# HalfA.net
KiCad netlist of a schematic drawn in EAGLE
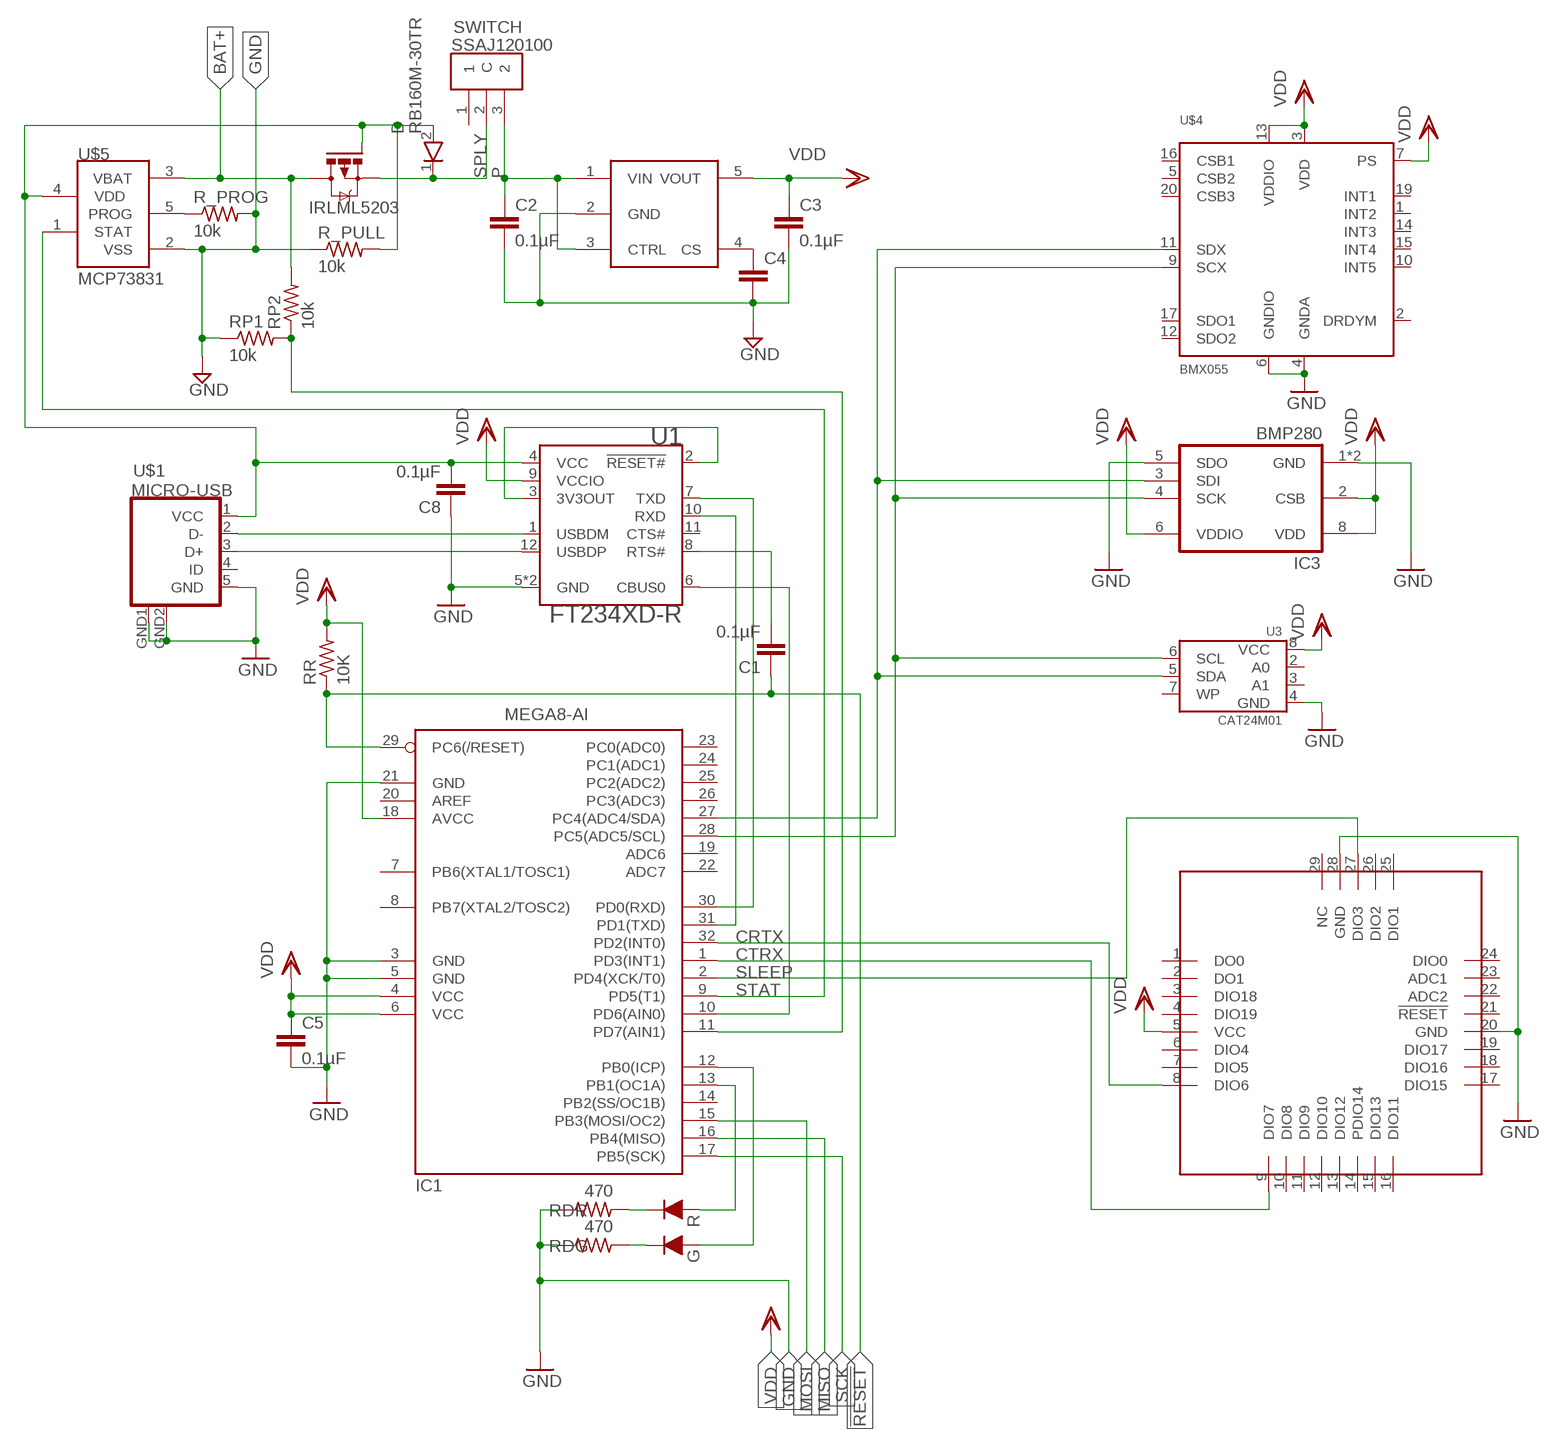
[diagram p0: schematic, sheet 1]

(export (version "E")
  (design (tool "Eeschema 10.0.6"))
  (components
    (comp (ref "C1")
      (value "0.1µF")
      (footprint "eagle-import:C0402K")
      (libsource (lib "eagle-import") (part "C-EUC0402K"))
    )
    (comp (ref "C2")
      (value "0.1µF")
      (footprint "eagle-import:C0402K")
      (libsource (lib "eagle-import") (part "C-EUC0402K"))
    )
    (comp (ref "C3")
      (value "0.1µF")
      (footprint "eagle-import:C0402K")
      (libsource (lib "eagle-import") (part "C-EUC0402K"))
    )
    (comp (ref "C4")
      (value "C-EUC0402K")
      (footprint "eagle-import:C0402K")
      (libsource (lib "eagle-import") (part "C-EUC0402K"))
    )
    (comp (ref "C5")
      (value "0.1µF")
      (footprint "eagle-import:C0402K")
      (libsource (lib "eagle-import") (part "C-EUC0402K"))
    )
    (comp (ref "C8")
      (value "0.1µF")
      (footprint "eagle-import:C0402K")
      (libsource (lib "eagle-import") (part "C-EUC0402K"))
    )
    (comp (ref "D")
      (value "RB160M-30TR")
      (footprint "eagle-import:SODFL3516X90N")
      (fields (field (name "MOUSER_PART_NUMBER") "755-RB160M-30TR") (field (name "RS_PART_NUMBER") "7526079"))
      (libsource (lib "eagle-import") (part "RB160M-30TR"))
    )
    (comp (ref "IC1")
      (value "MEGA8-AI")
      (footprint "eagle-import:TQFP32-08")
      (fields (field (name "MPN") "ATMEGA8-16AU"))
      (libsource (lib "eagle-import") (part "MEGA8-AI"))
    )
    (comp (ref "IC3")
      (value "BMP280")
      (footprint "eagle-import:BMP280")
      (libsource (lib "eagle-import") (part "BMP280"))
    )
    (comp (ref "Q1")
      (value "IRLML5203")
      (footprint "eagle-import:MICRO3")
      (libsource (lib "eagle-import") (part "IRLML5203"))
    )
    (comp (ref "RDG")
      (value "470")
      (footprint "eagle-import:R0402")
      (libsource (lib "eagle-import") (part "R-US_R0402"))
    )
    (comp (ref "RDR")
      (value "470")
      (footprint "eagle-import:R0402")
      (libsource (lib "eagle-import") (part "R-US_R0402"))
    )
    (comp (ref "RP1")
      (value "10k")
      (footprint "eagle-import:R0402")
      (libsource (lib "eagle-import") (part "R-US_R0402"))
    )
    (comp (ref "RP2")
      (value "10k")
      (footprint "eagle-import:R0402")
      (libsource (lib "eagle-import") (part "R-US_R0402"))
    )
    (comp (ref "RR")
      (value "10K")
      (footprint "eagle-import:R0402")
      (libsource (lib "eagle-import") (part "R-US_R0402"))
    )
    (comp (ref "R_PROG")
      (value "10k")
      (footprint "eagle-import:R0402")
      (libsource (lib "eagle-import") (part "R-US_R0402"))
    )
    (comp (ref "R_PULL")
      (value "10k")
      (footprint "eagle-import:R0402")
      (libsource (lib "eagle-import") (part "R-US_R0402"))
    )
    (comp (ref "SWITCH")
      (value "SSAJ120100")
      (footprint "eagle-import:SSAJ120100")
      (fields (field (name "MOUSER_PART_NUMBER") "688-SSAJ120100") (field (name "RS_PART_NUMBER") "1238892"))
      (libsource (lib "eagle-import") (part "SSAJ120100"))
    )
    (comp (ref "U$1")
      (value "MICRO-USB")
      (footprint "eagle-import:MICRO-USB")
      (libsource (lib "eagle-import") (part "MICRO-USB"))
    )
    (comp (ref "U$2")
      (value "NJM12888F")
      (footprint "eagle-import:NJM12888F")
      (libsource (lib "eagle-import") (part "NJM12888F"))
    )
    (comp (ref "U$3")
      (value "LITE")
      (footprint "eagle-import:LITE")
      (libsource (lib "eagle-import") (part "LITE"))
    )
    (comp (ref "U$4")
      (value "BMX055")
      (footprint "eagle-import:BMX055")
      (fields (field (name "DIGI-KEY_PART_NUMBER") "828-1060-1-ND") (field (name "MF") "Bosch Sensortec"))
      (libsource (lib "eagle-import") (part "BMX055"))
    )
    (comp (ref "U$5")
      (value "MCP73831")
      (footprint "eagle-import:SOT23-5L")
      (libsource (lib "eagle-import") (part "MCP73831"))
    )
    (comp (ref "U$6")
      (value "SML-P24MUW")
      (footprint "eagle-import:SML-P24MUW")
      (libsource (lib "eagle-import") (part "SML-P24MUW"))
    )
    (comp (ref "U1")
      (value "FT234XD-R")
      (footprint "eagle-import:SON45P300X300X80-13N")
      (fields (field (name "DIGI-KEY_PART_NUMBER") "768-1178-1-ND") (field (name "MF") "FTDI,"))
      (libsource (lib "eagle-import") (part "FT234XD-R"))
    )
    (comp (ref "U3")
      (value "CAT24M01")
      (footprint "eagle-import:SO-8")
      (fields (field (name "MF") "ON Semiconductor"))
      (libsource (lib "eagle-import") (part "CAT24M01"))
    )
  )
  (nets
    (net (code "1") (name "/CRTX") (class "Default")
      (node (ref "IC1") (pin "32") (pinfunction "PD2(INT0)_32") (pintype "bidirectional"))
      (node (ref "U$3") (pin "8") (pinfunction "DIO6_8") (pintype "bidirectional"))
    )
    (net (code "2") (name "/CTRX") (class "Default")
      (node (ref "IC1") (pin "1") (pinfunction "PD3(INT1)_1") (pintype "bidirectional"))
      (node (ref "U$3") (pin "9") (pinfunction "DIO7_9") (pintype "bidirectional"))
    )
    (net (code "3") (name "/P") (class "Default")
      (node (ref "C2") (pin "1") (pinfunction "1_1") (pintype "passive"))
      (node (ref "SWITCH") (pin "3") (pinfunction "2_3") (pintype "bidirectional"))
      (node (ref "U$2") (pin "1") (pinfunction "VIN_1") (pintype "power_in"))
      (node (ref "U$2") (pin "3") (pinfunction "CTRL_3") (pintype "input"))
    )
    (net (code "4") (name "/SLEEP") (class "Default")
      (node (ref "IC1") (pin "2") (pinfunction "PD4(XCK/T0)_2") (pintype "bidirectional"))
      (node (ref "U$3") (pin "27") (pinfunction "DIO3_27") (pintype "bidirectional"))
    )
    (net (code "5") (name "/SPLY") (class "Default")
      (node (ref "D") (pin "1") (pinfunction "K_1") (pintype "bidirectional"))
      (node (ref "Q1") (pin "2") (pinfunction "S_2") (pintype "passive"))
      (node (ref "SWITCH") (pin "2") (pinfunction "C_2") (pintype "bidirectional"))
    )
    (net (code "6") (name "/STAT") (class "Default")
      (node (ref "IC1") (pin "9") (pinfunction "PD5(T1)_9") (pintype "bidirectional"))
      (node (ref "U$5") (pin "1") (pinfunction "STAT_1") (pintype "bidirectional"))
    )
    (net (code "7") (name "/~{RESET}") (class "Default")
      (node (ref "C1") (pin "1") (pinfunction "1_1") (pintype "passive"))
      (node (ref "IC1") (pin "29") (pinfunction "PC6(/RESET)_29") (pintype "bidirectional"))
      (node (ref "RR") (pin "1") (pinfunction "1_1") (pintype "passive"))
    )
    (net (code "8") (name "BAT+") (class "Default")
      (node (ref "Q1") (pin "3") (pinfunction "D_3") (pintype "passive"))
      (node (ref "RP2") (pin "2") (pinfunction "2_2") (pintype "passive"))
      (node (ref "U$5") (pin "3") (pinfunction "VBAT_3") (pintype "bidirectional"))
    )
    (net (code "9") (name "GND") (class "Default")
      (node (ref "C2") (pin "2") (pinfunction "2_2") (pintype "passive"))
      (node (ref "C3") (pin "2") (pinfunction "2_2") (pintype "passive"))
      (node (ref "C4") (pin "2") (pinfunction "2_2") (pintype "passive"))
      (node (ref "C5") (pin "2") (pinfunction "2_2") (pintype "passive"))
      (node (ref "C8") (pin "1") (pinfunction "1_1") (pintype "passive"))
      (node (ref "IC1") (pin "21") (pinfunction "GND_21") (pintype "power_in"))
      (node (ref "IC1") (pin "3") (pinfunction "GND_3") (pintype "power_in"))
      (node (ref "IC1") (pin "5") (pinfunction "GND_5") (pintype "power_in"))
      (node (ref "IC3") (pin "1") (pinfunction "GND_1") (pintype "power_in"))
      (node (ref "IC3") (pin "5") (pinfunction "SDO_5") (pintype "input"))
      (node (ref "IC3") (pin "7") (pinfunction "GND_7") (pintype "power_in"))
      (node (ref "RDG") (pin "1") (pinfunction "1_1") (pintype "passive"))
      (node (ref "RDR") (pin "1") (pinfunction "1_1") (pintype "passive"))
      (node (ref "RP1") (pin "1") (pinfunction "1_1") (pintype "passive"))
      (node (ref "R_PROG") (pin "2") (pinfunction "2_2") (pintype "passive"))
      (node (ref "R_PULL") (pin "1") (pinfunction "1_1") (pintype "passive"))
      (node (ref "U$1") (pin "5") (pinfunction "GND_5") (pintype "power_in"))
      (node (ref "U$1") (pin "GND1") (pinfunction "GND_GND1") (pintype "power_in"))
      (node (ref "U$1") (pin "GND2") (pinfunction "GND_GND2") (pintype "power_in"))
      (node (ref "U$2") (pin "2") (pinfunction "GND_2") (pintype "power_in"))
      (node (ref "U$3") (pin "20") (pinfunction "GND_20") (pintype "power_in"))
      (node (ref "U$3") (pin "28") (pinfunction "GND_28") (pintype "power_in"))
      (node (ref "U$4") (pin "4") (pinfunction "GNDA_4") (pintype "bidirectional"))
      (node (ref "U$4") (pin "6") (pinfunction "GNDIO_6") (pintype "bidirectional"))
      (node (ref "U$5") (pin "2") (pinfunction "VSS_2") (pintype "bidirectional"))
      (node (ref "U1") (pin "13") (pinfunction "GND_13") (pintype "power_in"))
      (node (ref "U1") (pin "5") (pinfunction "GND_5") (pintype "power_in"))
      (node (ref "U3") (pin "4") (pinfunction "GND_4") (pintype "bidirectional"))
    )
    (net (code "10") (name "MISO") (class "Default")
      (node (ref "IC1") (pin "16") (pinfunction "PB4(MISO)_16") (pintype "bidirectional"))
    )
    (net (code "11") (name "MOSI") (class "Default")
      (node (ref "IC1") (pin "15") (pinfunction "PB3(MOSI/OC2)_15") (pintype "bidirectional"))
    )
    (net (code "12") (name "Net-(D-A)") (class "Default")
      (node (ref "C8") (pin "2") (pinfunction "2_2") (pintype "passive"))
      (node (ref "D") (pin "2") (pinfunction "A_2") (pintype "bidirectional"))
      (node (ref "Q1") (pin "1") (pinfunction "G_1") (pintype "passive"))
      (node (ref "R_PULL") (pin "2") (pinfunction "2_2") (pintype "passive"))
      (node (ref "U$1") (pin "1") (pinfunction "VCC_1") (pintype "power_in"))
      (node (ref "U$5") (pin "4") (pinfunction "VDD_4") (pintype "bidirectional"))
      (node (ref "U1") (pin "4") (pinfunction "VCC_4") (pintype "power_in"))
    )
    (net (code "13") (name "Net-(IC1-PB0(ICP))") (class "Default")
      (node (ref "IC1") (pin "12") (pinfunction "PB0(ICP)_12") (pintype "bidirectional"))
      (node (ref "U$6") (pin "1") (pinfunction "GA_1") (pintype "power_in"))
    )
    (net (code "14") (name "Net-(IC1-PB1(OC1A))") (class "Default")
      (node (ref "IC1") (pin "13") (pinfunction "PB1(OC1A)_13") (pintype "bidirectional"))
      (node (ref "U$6") (pin "2") (pinfunction "RA_2") (pintype "power_in"))
    )
    (net (code "15") (name "Net-(IC1-PC4(ADC4{slash}SDA))") (class "Default")
      (node (ref "IC1") (pin "27") (pinfunction "PC4(ADC4/SDA)_27") (pintype "bidirectional"))
      (node (ref "IC3") (pin "3") (pinfunction "SDI_3") (pintype "bidirectional"))
      (node (ref "U$4") (pin "11") (pinfunction "SDX_11") (pintype "bidirectional"))
      (node (ref "U3") (pin "5") (pinfunction "SDA_5") (pintype "bidirectional"))
    )
    (net (code "16") (name "Net-(IC1-PC5(ADC5{slash}SCL))") (class "Default")
      (node (ref "IC1") (pin "28") (pinfunction "PC5(ADC5/SCL)_28") (pintype "bidirectional"))
      (node (ref "IC3") (pin "4") (pinfunction "SCK_4") (pintype "bidirectional"))
      (node (ref "U$4") (pin "9") (pinfunction "SCX_9") (pintype "bidirectional"))
      (node (ref "U3") (pin "6") (pinfunction "SCL_6") (pintype "bidirectional"))
    )
    (net (code "17") (name "Net-(IC1-PD0(RXD))") (class "Default")
      (node (ref "IC1") (pin "30") (pinfunction "PD0(RXD)_30") (pintype "bidirectional"))
      (node (ref "U1") (pin "7") (pinfunction "TXD_7") (pintype "output"))
    )
    (net (code "18") (name "Net-(IC1-PD1(TXD))") (class "Default")
      (node (ref "IC1") (pin "31") (pinfunction "PD1(TXD)_31") (pintype "bidirectional"))
      (node (ref "U1") (pin "10") (pinfunction "RXD_10") (pintype "input"))
    )
    (net (code "19") (name "Net-(IC1-PD6(AIN0))") (class "Default")
      (node (ref "IC1") (pin "10") (pinfunction "PD6(AIN0)_10") (pintype "bidirectional"))
      (node (ref "U1") (pin "6") (pinfunction "CBUS0_6") (pintype "bidirectional"))
    )
    (net (code "20") (name "Net-(IC1-PD7(AIN1))") (class "Default")
      (node (ref "IC1") (pin "11") (pinfunction "PD7(AIN1)_11") (pintype "bidirectional"))
      (node (ref "RP1") (pin "2") (pinfunction "2_2") (pintype "passive"))
      (node (ref "RP2") (pin "1") (pinfunction "1_1") (pintype "passive"))
    )
    (net (code "21") (name "Net-(U$1-D+)") (class "Default")
      (node (ref "U$1") (pin "3") (pinfunction "D+_3") (pintype "bidirectional"))
      (node (ref "U1") (pin "12") (pinfunction "USBDP_12") (pintype "bidirectional"))
    )
    (net (code "22") (name "Net-(U$1-D-)") (class "Default")
      (node (ref "U$1") (pin "2") (pinfunction "D-_2") (pintype "bidirectional"))
      (node (ref "U1") (pin "1") (pinfunction "USBDM_1") (pintype "bidirectional"))
    )
    (net (code "23") (name "Net-(U$2-CS)") (class "Default")
      (node (ref "C4") (pin "1") (pinfunction "1_1") (pintype "passive"))
      (node (ref "U$2") (pin "4") (pinfunction "CS_4") (pintype "input"))
    )
    (net (code "24") (name "Net-(U$5-PROG)") (class "Default")
      (node (ref "R_PROG") (pin "1") (pinfunction "1_1") (pintype "passive"))
      (node (ref "U$5") (pin "5") (pinfunction "PROG_5") (pintype "bidirectional"))
    )
    (net (code "25") (name "Net-(U$6-GC)") (class "Default")
      (node (ref "RDG") (pin "2") (pinfunction "2_2") (pintype "passive"))
      (node (ref "U$6") (pin "4") (pinfunction "GC_4") (pintype "power_in"))
    )
    (net (code "26") (name "Net-(U$6-RC)") (class "Default")
      (node (ref "RDR") (pin "2") (pinfunction "2_2") (pintype "passive"))
      (node (ref "U$6") (pin "3") (pinfunction "RC_3") (pintype "power_in"))
    )
    (net (code "27") (name "Net-(U1-3V3OUT)") (class "Default")
      (node (ref "U1") (pin "2") (pinfunction "~{RESET#}_2") (pintype "input"))
      (node (ref "U1") (pin "3") (pinfunction "3V3OUT_3") (pintype "power_in"))
    )
    (net (code "28") (name "Net-(U1-RTS#)") (class "Default")
      (node (ref "C1") (pin "2") (pinfunction "2_2") (pintype "passive"))
      (node (ref "U1") (pin "8") (pinfunction "RTS#_8") (pintype "output"))
    )
    (net (code "29") (name "SCK") (class "Default")
      (node (ref "IC1") (pin "17") (pinfunction "PB5(SCK)_17") (pintype "bidirectional"))
    )
    (net (code "30") (name "VDD") (class "Default")
      (node (ref "C3") (pin "1") (pinfunction "1_1") (pintype "passive"))
      (node (ref "C5") (pin "1") (pinfunction "1_1") (pintype "passive"))
      (node (ref "IC1") (pin "18") (pinfunction "AVCC_18") (pintype "power_in"))
      (node (ref "IC1") (pin "4") (pinfunction "VCC_4") (pintype "power_in"))
      (node (ref "IC1") (pin "6") (pinfunction "VCC_6") (pintype "power_in"))
      (node (ref "IC3") (pin "2") (pinfunction "CSB_2") (pintype "input"))
      (node (ref "IC3") (pin "6") (pinfunction "VDDIO_6") (pintype "power_in"))
      (node (ref "IC3") (pin "8") (pinfunction "VDD_8") (pintype "power_in"))
      (node (ref "RR") (pin "2") (pinfunction "2_2") (pintype "passive"))
      (node (ref "U$2") (pin "5") (pinfunction "VOUT_5") (pintype "power_in"))
      (node (ref "U$3") (pin "5") (pinfunction "VCC_5") (pintype "power_in"))
      (node (ref "U$4") (pin "13") (pinfunction "VDDIO_13") (pintype "bidirectional"))
      (node (ref "U$4") (pin "3") (pinfunction "VDD_3") (pintype "bidirectional"))
      (node (ref "U$4") (pin "7") (pinfunction "PS_7") (pintype "bidirectional"))
      (node (ref "U1") (pin "9") (pinfunction "VCCIO_9") (pintype "power_in"))
      (node (ref "U3") (pin "8") (pinfunction "VCC_8") (pintype "bidirectional"))
    )
    (net (code "31") (name "unconnected-(IC1-ADC6-Pad19)") (class "Default")
      (node (ref "IC1") (pin "19") (pinfunction "ADC6_19") (pintype "bidirectional"))
    )
    (net (code "32") (name "unconnected-(IC1-ADC7-Pad22)") (class "Default")
      (node (ref "IC1") (pin "22") (pinfunction "ADC7_22") (pintype "bidirectional"))
    )
    (net (code "33") (name "unconnected-(IC1-AREF-Pad20)") (class "Default")
      (node (ref "IC1") (pin "20") (pinfunction "AREF_20") (pintype "passive"))
    )
    (net (code "34") (name "unconnected-(IC1-PB2(SS{slash}OC1B)-Pad14)") (class "Default")
      (node (ref "IC1") (pin "14") (pinfunction "PB2(SS/OC1B)_14") (pintype "bidirectional"))
    )
    (net (code "35") (name "unconnected-(IC1-PB6(XTAL1{slash}TOSC1)-Pad7)") (class "Default")
      (node (ref "IC1") (pin "7") (pinfunction "PB6(XTAL1/TOSC1)_7") (pintype "bidirectional"))
    )
    (net (code "36") (name "unconnected-(IC1-PB7(XTAL2{slash}TOSC2)-Pad8)") (class "Default")
      (node (ref "IC1") (pin "8") (pinfunction "PB7(XTAL2/TOSC2)_8") (pintype "bidirectional"))
    )
    (net (code "37") (name "unconnected-(IC1-PC0(ADC0)-Pad23)") (class "Default")
      (node (ref "IC1") (pin "23") (pinfunction "PC0(ADC0)_23") (pintype "bidirectional"))
    )
    (net (code "38") (name "unconnected-(IC1-PC1(ADC1)-Pad24)") (class "Default")
      (node (ref "IC1") (pin "24") (pinfunction "PC1(ADC1)_24") (pintype "bidirectional"))
    )
    (net (code "39") (name "unconnected-(IC1-PC2(ADC2)-Pad25)") (class "Default")
      (node (ref "IC1") (pin "25") (pinfunction "PC2(ADC2)_25") (pintype "bidirectional"))
    )
    (net (code "40") (name "unconnected-(IC1-PC3(ADC3)-Pad26)") (class "Default")
      (node (ref "IC1") (pin "26") (pinfunction "PC3(ADC3)_26") (pintype "bidirectional"))
    )
    (net (code "41") (name "unconnected-(SWITCH-Pad1)") (class "Default")
      (node (ref "SWITCH") (pin "1") (pinfunction "1_1") (pintype "bidirectional"))
    )
    (net (code "42") (name "unconnected-(U$1-ID-Pad4)") (class "Default")
      (node (ref "U$1") (pin "4") (pinfunction "ID_4") (pintype "bidirectional"))
    )
    (net (code "43") (name "unconnected-(U$3-ADC1-Pad23)") (class "Default")
      (node (ref "U$3") (pin "23") (pinfunction "ADC1_23") (pintype "bidirectional"))
    )
    (net (code "44") (name "unconnected-(U$3-ADC2-Pad22)") (class "Default")
      (node (ref "U$3") (pin "22") (pinfunction "ADC2_22") (pintype "bidirectional"))
    )
    (net (code "45") (name "unconnected-(U$3-DIO0-Pad24)") (class "Default")
      (node (ref "U$3") (pin "24") (pinfunction "DIO0_24") (pintype "bidirectional"))
    )
    (net (code "46") (name "unconnected-(U$3-DIO1-Pad25)") (class "Default")
      (node (ref "U$3") (pin "25") (pinfunction "DIO1_25") (pintype "bidirectional"))
    )
    (net (code "47") (name "unconnected-(U$3-DIO2-Pad26)") (class "Default")
      (node (ref "U$3") (pin "26") (pinfunction "DIO2_26") (pintype "bidirectional"))
    )
    (net (code "48") (name "unconnected-(U$3-DIO4-Pad6)") (class "Default")
      (node (ref "U$3") (pin "6") (pinfunction "DIO4_6") (pintype "bidirectional"))
    )
    (net (code "49") (name "unconnected-(U$3-DIO5-Pad7)") (class "Default")
      (node (ref "U$3") (pin "7") (pinfunction "DIO5_7") (pintype "bidirectional"))
    )
    (net (code "50") (name "unconnected-(U$3-DIO8-Pad10)") (class "Default")
      (node (ref "U$3") (pin "10") (pinfunction "DIO8_10") (pintype "bidirectional"))
    )
    (net (code "51") (name "unconnected-(U$3-DIO9-Pad11)") (class "Default")
      (node (ref "U$3") (pin "11") (pinfunction "DIO9_11") (pintype "bidirectional"))
    )
    (net (code "52") (name "unconnected-(U$3-DIO10-Pad12)") (class "Default")
      (node (ref "U$3") (pin "12") (pinfunction "DIO10_12") (pintype "bidirectional"))
    )
    (net (code "53") (name "unconnected-(U$3-DIO11-Pad16)") (class "Default")
      (node (ref "U$3") (pin "16") (pinfunction "DIO11_16") (pintype "bidirectional"))
    )
    (net (code "54") (name "unconnected-(U$3-DIO12-Pad13)") (class "Default")
      (node (ref "U$3") (pin "13") (pinfunction "DIO12_13") (pintype "bidirectional"))
    )
    (net (code "55") (name "unconnected-(U$3-DIO13-Pad15)") (class "Default")
      (node (ref "U$3") (pin "15") (pinfunction "DIO13_15") (pintype "bidirectional"))
    )
    (net (code "56") (name "unconnected-(U$3-DIO15-Pad17)") (class "Default")
      (node (ref "U$3") (pin "17") (pinfunction "DIO15_17") (pintype "bidirectional"))
    )
    (net (code "57") (name "unconnected-(U$3-DIO16-Pad18)") (class "Default")
      (node (ref "U$3") (pin "18") (pinfunction "DIO16_18") (pintype "bidirectional"))
    )
    (net (code "58") (name "unconnected-(U$3-DIO17-Pad19)") (class "Default")
      (node (ref "U$3") (pin "19") (pinfunction "DIO17_19") (pintype "bidirectional"))
    )
    (net (code "59") (name "unconnected-(U$3-DIO18-Pad3)") (class "Default")
      (node (ref "U$3") (pin "3") (pinfunction "DIO18_3") (pintype "bidirectional"))
    )
    (net (code "60") (name "unconnected-(U$3-DIO19-Pad4)") (class "Default")
      (node (ref "U$3") (pin "4") (pinfunction "DIO19_4") (pintype "bidirectional"))
    )
    (net (code "61") (name "unconnected-(U$3-DO0-Pad1)") (class "Default")
      (node (ref "U$3") (pin "1") (pinfunction "DO0_1") (pintype "output"))
    )
    (net (code "62") (name "unconnected-(U$3-DO1-Pad2)") (class "Default")
      (node (ref "U$3") (pin "2") (pinfunction "DO1_2") (pintype "bidirectional"))
    )
    (net (code "63") (name "unconnected-(U$3-NC-Pad29)") (class "Default")
      (node (ref "U$3") (pin "29") (pinfunction "NC_29") (pintype "no_connect"))
    )
    (net (code "64") (name "unconnected-(U$3-PDIO14-Pad14)") (class "Default")
      (node (ref "U$3") (pin "14") (pinfunction "PDIO14_14") (pintype "bidirectional"))
    )
    (net (code "65") (name "unconnected-(U$3-~{RESET}-Pad21)") (class "Default")
      (node (ref "U$3") (pin "21") (pinfunction "~{RESET}_21") (pintype "input"))
    )
    (net (code "66") (name "unconnected-(U$4-CSB1-Pad16)") (class "Default")
      (node (ref "U$4") (pin "16") (pinfunction "CSB1_16") (pintype "bidirectional"))
    )
    (net (code "67") (name "unconnected-(U$4-CSB2-Pad5)") (class "Default")
      (node (ref "U$4") (pin "5") (pinfunction "CSB2_5") (pintype "bidirectional"))
    )
    (net (code "68") (name "unconnected-(U$4-CSB3-Pad20)") (class "Default")
      (node (ref "U$4") (pin "20") (pinfunction "CSB3_20") (pintype "bidirectional"))
    )
    (net (code "69") (name "unconnected-(U$4-DRDYM-Pad2)") (class "Default")
      (node (ref "U$4") (pin "2") (pinfunction "DRDYM_2") (pintype "bidirectional"))
    )
    (net (code "70") (name "unconnected-(U$4-INT1-Pad19)") (class "Default")
      (node (ref "U$4") (pin "19") (pinfunction "INT1_19") (pintype "bidirectional"))
    )
    (net (code "71") (name "unconnected-(U$4-INT2-Pad1)") (class "Default")
      (node (ref "U$4") (pin "1") (pinfunction "INT2_1") (pintype "bidirectional"))
    )
    (net (code "72") (name "unconnected-(U$4-INT3-Pad14)") (class "Default")
      (node (ref "U$4") (pin "14") (pinfunction "INT3_14") (pintype "bidirectional"))
    )
    (net (code "73") (name "unconnected-(U$4-INT4-Pad15)") (class "Default")
      (node (ref "U$4") (pin "15") (pinfunction "INT4_15") (pintype "bidirectional"))
    )
    (net (code "74") (name "unconnected-(U$4-INT5-Pad10)") (class "Default")
      (node (ref "U$4") (pin "10") (pinfunction "INT5_10") (pintype "bidirectional"))
    )
    (net (code "75") (name "unconnected-(U$4-SDO1-Pad17)") (class "Default")
      (node (ref "U$4") (pin "17") (pinfunction "SDO1_17") (pintype "bidirectional"))
    )
    (net (code "76") (name "unconnected-(U$4-SDO2-Pad12)") (class "Default")
      (node (ref "U$4") (pin "12") (pinfunction "SDO2_12") (pintype "bidirectional"))
    )
    (net (code "77") (name "unconnected-(U1-CTS#-Pad11)") (class "Default")
      (node (ref "U1") (pin "11") (pinfunction "CTS#_11") (pintype "input"))
    )
    (net (code "78") (name "unconnected-(U3-A0-Pad2)") (class "Default")
      (node (ref "U3") (pin "2") (pinfunction "A0_2") (pintype "bidirectional"))
    )
    (net (code "79") (name "unconnected-(U3-A1-Pad3)") (class "Default")
      (node (ref "U3") (pin "3") (pinfunction "A1_3") (pintype "bidirectional"))
    )
    (net (code "80") (name "unconnected-(U3-WP-Pad7)") (class "Default")
      (node (ref "U3") (pin "7") (pinfunction "WP_7") (pintype "bidirectional"))
    )
  )
)
